# LTC6802.net
KiCad netlist of a schematic drawn in Altium Designer
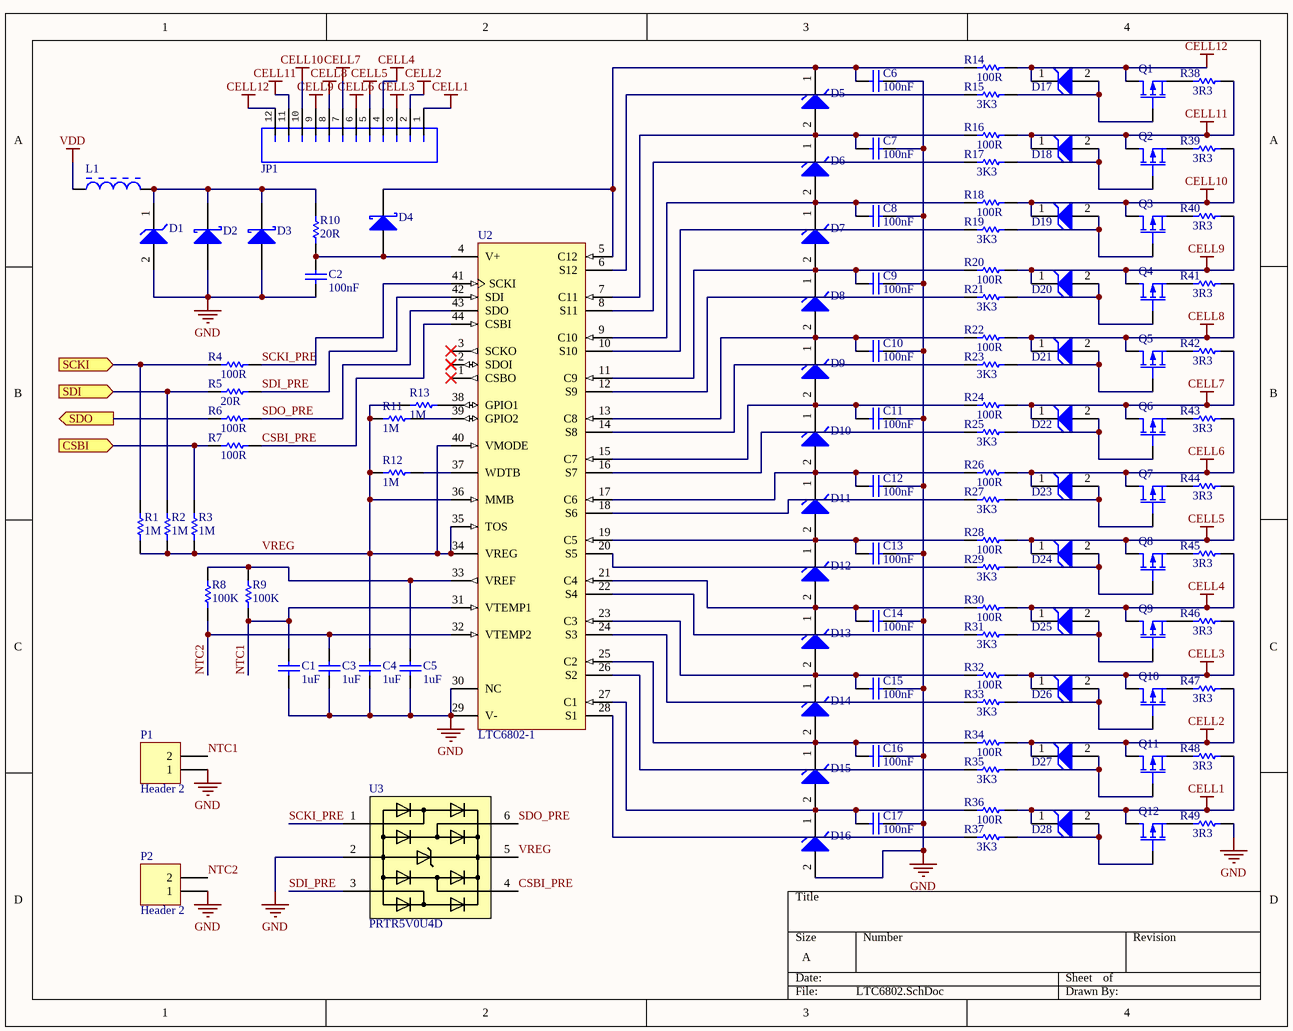
[diagram p0: LTC6802.SchDoc]

(export (version "E")
  (design (tool "Eeschema 10.0.6"))
  (components
    (comp (ref "C1")
      (value "1uF")
      (footprint "CAPC0603(1608)100_L")
      (description "CAP 1uF 6.3V Â±10% 0603 (1608 Metric) Thickness 1mm SMD")
      (fields (field (name "TOLERANCE") "Â±10%"))
      (libsource (lib "Altium Content Vault") (part "CAP"))
    )
    (comp (ref "C2")
      (value "100nF")
      (footprint "CAPC0603(1608)100_M")
      (description "CAP 100nF 100V Â±10% 0603 (1608 Metric) Thickness 1mm SMD")
      (fields (field (name "TOLERANCE") "Â±10%"))
      (libsource (lib "Altium Content Vault") (part "CAP"))
    )
    (comp (ref "C3")
      (value "1uF")
      (footprint "CAPC0603(1608)100_L")
      (description "CAP 1uF 6.3V Â±10% 0603 (1608 Metric) Thickness 1mm SMD")
      (fields (field (name "TOLERANCE") "Â±10%"))
      (libsource (lib "Altium Content Vault") (part "CAP"))
    )
    (comp (ref "C4")
      (value "1uF")
      (footprint "CAPC0603(1608)100_L")
      (description "CAP 1uF 6.3V Â±10% 0603 (1608 Metric) Thickness 1mm SMD")
      (fields (field (name "TOLERANCE") "Â±10%"))
      (libsource (lib "Altium Content Vault") (part "CAP"))
    )
    (comp (ref "C5")
      (value "1uF")
      (footprint "CAPC0603(1608)100_L")
      (description "CAP 1uF 6.3V Â±10% 0603 (1608 Metric) Thickness 1mm SMD")
      (fields (field (name "TOLERANCE") "Â±10%"))
      (libsource (lib "Altium Content Vault") (part "CAP"))
    )
    (comp (ref "C6")
      (value "100nF")
      (footprint "CAPC0603(1608)100_N")
      (description "CAP 100nF 6.3V Â±5% 0603 (1608 Metric) Thickness 1mm SMD")
      (fields (field (name "TOLERANCE") "Â±5%"))
      (libsource (lib "Altium Content Vault") (part "CAP"))
    )
    (comp (ref "C7")
      (value "100nF")
      (footprint "CAPC0603(1608)100_N")
      (description "CAP 100nF 6.3V Â±5% 0603 (1608 Metric) Thickness 1mm SMD")
      (fields (field (name "TOLERANCE") "Â±5%"))
      (libsource (lib "Altium Content Vault") (part "CAP"))
    )
    (comp (ref "C8")
      (value "100nF")
      (footprint "CAPC0603(1608)100_N")
      (description "CAP 100nF 6.3V Â±5% 0603 (1608 Metric) Thickness 1mm SMD")
      (fields (field (name "TOLERANCE") "Â±5%"))
      (libsource (lib "Altium Content Vault") (part "CAP"))
    )
    (comp (ref "C9")
      (value "100nF")
      (footprint "CAPC0603(1608)100_N")
      (description "CAP 100nF 6.3V Â±5% 0603 (1608 Metric) Thickness 1mm SMD")
      (fields (field (name "TOLERANCE") "Â±5%"))
      (libsource (lib "Altium Content Vault") (part "CAP"))
    )
    (comp (ref "C10")
      (value "100nF")
      (footprint "CAPC0603(1608)100_N")
      (description "CAP 100nF 6.3V Â±5% 0603 (1608 Metric) Thickness 1mm SMD")
      (fields (field (name "TOLERANCE") "Â±5%"))
      (libsource (lib "Altium Content Vault") (part "CAP"))
    )
    (comp (ref "C11")
      (value "100nF")
      (footprint "CAPC0603(1608)100_N")
      (description "CAP 100nF 6.3V Â±5% 0603 (1608 Metric) Thickness 1mm SMD")
      (fields (field (name "TOLERANCE") "Â±5%"))
      (libsource (lib "Altium Content Vault") (part "CAP"))
    )
    (comp (ref "C12")
      (value "100nF")
      (footprint "CAPC0603(1608)100_N")
      (description "CAP 100nF 6.3V Â±5% 0603 (1608 Metric) Thickness 1mm SMD")
      (fields (field (name "TOLERANCE") "Â±5%"))
      (libsource (lib "Altium Content Vault") (part "CAP"))
    )
    (comp (ref "C13")
      (value "100nF")
      (footprint "CAPC0603(1608)100_N")
      (description "CAP 100nF 6.3V Â±5% 0603 (1608 Metric) Thickness 1mm SMD")
      (fields (field (name "TOLERANCE") "Â±5%"))
      (libsource (lib "Altium Content Vault") (part "CAP"))
    )
    (comp (ref "C14")
      (value "100nF")
      (footprint "CAPC0603(1608)100_N")
      (description "CAP 100nF 6.3V Â±5% 0603 (1608 Metric) Thickness 1mm SMD")
      (fields (field (name "TOLERANCE") "Â±5%"))
      (libsource (lib "Altium Content Vault") (part "CAP"))
    )
    (comp (ref "C15")
      (value "100nF")
      (footprint "CAPC0603(1608)100_N")
      (description "CAP 100nF 6.3V Â±5% 0603 (1608 Metric) Thickness 1mm SMD")
      (fields (field (name "TOLERANCE") "Â±5%"))
      (libsource (lib "Altium Content Vault") (part "CAP"))
    )
    (comp (ref "C16")
      (value "100nF")
      (footprint "CAPC0603(1608)100_N")
      (description "CAP 100nF 6.3V Â±5% 0603 (1608 Metric) Thickness 1mm SMD")
      (fields (field (name "TOLERANCE") "Â±5%"))
      (libsource (lib "Altium Content Vault") (part "CAP"))
    )
    (comp (ref "C17")
      (value "100nF")
      (footprint "CAPC0603(1608)100_N")
      (description "CAP 100nF 6.3V Â±5% 0603 (1608 Metric) Thickness 1mm SMD")
      (fields (field (name "TOLERANCE") "Â±5%"))
      (libsource (lib "Altium Content Vault") (part "CAP"))
    )
    (comp (ref "D1") (value "~") (footprint "SOD-123") (libsource (lib "Components") (part "CMHZ5265B")))
    (comp (ref "D2")
      (value "~")
      (footprint "DIOD-SOD-123-2_V")
      (description "Surface Mount Schottky Barrier Diode, 100 V, -55 to 125 degC, 2-Pin SOD123, RoHS, Tape and Reel")
      (fields (field (name "PARTNUMBER") "BAT46W-7-F") (field (name "MANUFACTURER") "Diodes Inc"))
      (libsource (lib "Altium Content Vault") (part "DIOD-DSKY-A1K2-2"))
    )
    (comp (ref "D3")
      (value "~")
      (footprint "DIOD-SOD-123-2_V")
      (description "Surface Mount Schottky Barrier Diode, 100 V, -55 to 125 degC, 2-Pin SOD123, RoHS, Tape and Reel")
      (fields (field (name "PARTNUMBER") "BAT46W-7-F") (field (name "MANUFACTURER") "Diodes Inc"))
      (libsource (lib "Altium Content Vault") (part "DIOD-DSKY-A1K2-2"))
    )
    (comp (ref "D4")
      (value "~")
      (footprint "DIOD-SOD-123-2_V")
      (description "Surface Mount Schottky Barrier Diode, 100 V, -55 to 125 degC, 2-Pin SOD123, RoHS, Tape and Reel")
      (fields (field (name "PARTNUMBER") "BAT46W-7-F") (field (name "MANUFACTURER") "Diodes Inc"))
      (libsource (lib "Altium Content Vault") (part "DIOD-DSKY-A1K2-2"))
    )
    (comp (ref "D5")
      (value "~")
      (footprint "ONSC-SOD-323-2-477-02_V")
      (description "Zener Voltage Regulator, 300 mW, 2-Pin SOD-323, Tape and Reel")
      (fields (field (name "MANUFACTURER") "On Semiconductor") (field (name "PARTNUMBER") "MM3Z12VT1"))
      (libsource (lib "Altium Content Vault") (part "ONSC-K1A2-2"))
    )
    (comp (ref "D6")
      (value "~")
      (footprint "ONSC-SOD-323-2-477-02_V")
      (description "Zener Voltage Regulator, 300 mW, 2-Pin SOD-323, Tape and Reel")
      (fields (field (name "MANUFACTURER") "On Semiconductor") (field (name "PARTNUMBER") "MM3Z12VT1"))
      (libsource (lib "Altium Content Vault") (part "ONSC-K1A2-2"))
    )
    (comp (ref "D7")
      (value "~")
      (footprint "ONSC-SOD-323-2-477-02_V")
      (description "Zener Voltage Regulator, 300 mW, 2-Pin SOD-323, Tape and Reel")
      (fields (field (name "MANUFACTURER") "On Semiconductor") (field (name "PARTNUMBER") "MM3Z12VT1"))
      (libsource (lib "Altium Content Vault") (part "ONSC-K1A2-2"))
    )
    (comp (ref "D8")
      (value "~")
      (footprint "ONSC-SOD-323-2-477-02_V")
      (description "Zener Voltage Regulator, 300 mW, 2-Pin SOD-323, Tape and Reel")
      (fields (field (name "MANUFACTURER") "On Semiconductor") (field (name "PARTNUMBER") "MM3Z12VT1"))
      (libsource (lib "Altium Content Vault") (part "ONSC-K1A2-2"))
    )
    (comp (ref "D9")
      (value "~")
      (footprint "ONSC-SOD-323-2-477-02_V")
      (description "Zener Voltage Regulator, 300 mW, 2-Pin SOD-323, Tape and Reel")
      (fields (field (name "MANUFACTURER") "On Semiconductor") (field (name "PARTNUMBER") "MM3Z12VT1"))
      (libsource (lib "Altium Content Vault") (part "ONSC-K1A2-2"))
    )
    (comp (ref "D10")
      (value "~")
      (footprint "ONSC-SOD-323-2-477-02_V")
      (description "Zener Voltage Regulator, 300 mW, 2-Pin SOD-323, Tape and Reel")
      (fields (field (name "MANUFACTURER") "On Semiconductor") (field (name "PARTNUMBER") "MM3Z12VT1"))
      (libsource (lib "Altium Content Vault") (part "ONSC-K1A2-2"))
    )
    (comp (ref "D11")
      (value "~")
      (footprint "ONSC-SOD-323-2-477-02_V")
      (description "Zener Voltage Regulator, 300 mW, 2-Pin SOD-323, Tape and Reel")
      (fields (field (name "MANUFACTURER") "On Semiconductor") (field (name "PARTNUMBER") "MM3Z12VT1"))
      (libsource (lib "Altium Content Vault") (part "ONSC-K1A2-2"))
    )
    (comp (ref "D12")
      (value "~")
      (footprint "ONSC-SOD-323-2-477-02_V")
      (description "Zener Voltage Regulator, 300 mW, 2-Pin SOD-323, Tape and Reel")
      (fields (field (name "MANUFACTURER") "On Semiconductor") (field (name "PARTNUMBER") "MM3Z12VT1"))
      (libsource (lib "Altium Content Vault") (part "ONSC-K1A2-2"))
    )
    (comp (ref "D13")
      (value "~")
      (footprint "ONSC-SOD-323-2-477-02_V")
      (description "Zener Voltage Regulator, 300 mW, 2-Pin SOD-323, Tape and Reel")
      (fields (field (name "MANUFACTURER") "On Semiconductor") (field (name "PARTNUMBER") "MM3Z12VT1"))
      (libsource (lib "Altium Content Vault") (part "ONSC-K1A2-2"))
    )
    (comp (ref "D14")
      (value "~")
      (footprint "ONSC-SOD-323-2-477-02_V")
      (description "Zener Voltage Regulator, 300 mW, 2-Pin SOD-323, Tape and Reel")
      (fields (field (name "MANUFACTURER") "On Semiconductor") (field (name "PARTNUMBER") "MM3Z12VT1"))
      (libsource (lib "Altium Content Vault") (part "ONSC-K1A2-2"))
    )
    (comp (ref "D15")
      (value "~")
      (footprint "ONSC-SOD-323-2-477-02_V")
      (description "Zener Voltage Regulator, 300 mW, 2-Pin SOD-323, Tape and Reel")
      (fields (field (name "MANUFACTURER") "On Semiconductor") (field (name "PARTNUMBER") "MM3Z12VT1"))
      (libsource (lib "Altium Content Vault") (part "ONSC-K1A2-2"))
    )
    (comp (ref "D16")
      (value "~")
      (footprint "ONSC-SOD-323-2-477-02_V")
      (description "Zener Voltage Regulator, 300 mW, 2-Pin SOD-323, Tape and Reel")
      (fields (field (name "MANUFACTURER") "On Semiconductor") (field (name "PARTNUMBER") "MM3Z12VT1"))
      (libsource (lib "Altium Content Vault") (part "ONSC-K1A2-2"))
    )
    (comp (ref "D17")
      (value "~")
      (footprint "ONSC-SOD-323-2-477-02_V")
      (description "Zener Voltage Regulator, 300 mW, 2-Pin SOD-323, Tape and Reel")
      (fields (field (name "MANUFACTURER") "On Semiconductor") (field (name "PARTNUMBER") "MM3Z12VT1"))
      (libsource (lib "Altium Content Vault") (part "ONSC-K1A2-2"))
    )
    (comp (ref "D18")
      (value "~")
      (footprint "ONSC-SOD-323-2-477-02_V")
      (description "Zener Voltage Regulator, 300 mW, 2-Pin SOD-323, Tape and Reel")
      (fields (field (name "MANUFACTURER") "On Semiconductor") (field (name "PARTNUMBER") "MM3Z12VT1"))
      (libsource (lib "Altium Content Vault") (part "ONSC-K1A2-2"))
    )
    (comp (ref "D19")
      (value "~")
      (footprint "ONSC-SOD-323-2-477-02_V")
      (description "Zener Voltage Regulator, 300 mW, 2-Pin SOD-323, Tape and Reel")
      (fields (field (name "MANUFACTURER") "On Semiconductor") (field (name "PARTNUMBER") "MM3Z12VT1"))
      (libsource (lib "Altium Content Vault") (part "ONSC-K1A2-2"))
    )
    (comp (ref "D20")
      (value "~")
      (footprint "ONSC-SOD-323-2-477-02_V")
      (description "Zener Voltage Regulator, 300 mW, 2-Pin SOD-323, Tape and Reel")
      (fields (field (name "MANUFACTURER") "On Semiconductor") (field (name "PARTNUMBER") "MM3Z12VT1"))
      (libsource (lib "Altium Content Vault") (part "ONSC-K1A2-2"))
    )
    (comp (ref "D21")
      (value "~")
      (footprint "ONSC-SOD-323-2-477-02_V")
      (description "Zener Voltage Regulator, 300 mW, 2-Pin SOD-323, Tape and Reel")
      (fields (field (name "MANUFACTURER") "On Semiconductor") (field (name "PARTNUMBER") "MM3Z12VT1"))
      (libsource (lib "Altium Content Vault") (part "ONSC-K1A2-2"))
    )
    (comp (ref "D22")
      (value "~")
      (footprint "ONSC-SOD-323-2-477-02_V")
      (description "Zener Voltage Regulator, 300 mW, 2-Pin SOD-323, Tape and Reel")
      (fields (field (name "MANUFACTURER") "On Semiconductor") (field (name "PARTNUMBER") "MM3Z12VT1"))
      (libsource (lib "Altium Content Vault") (part "ONSC-K1A2-2"))
    )
    (comp (ref "D23")
      (value "~")
      (footprint "ONSC-SOD-323-2-477-02_V")
      (description "Zener Voltage Regulator, 300 mW, 2-Pin SOD-323, Tape and Reel")
      (fields (field (name "MANUFACTURER") "On Semiconductor") (field (name "PARTNUMBER") "MM3Z12VT1"))
      (libsource (lib "Altium Content Vault") (part "ONSC-K1A2-2"))
    )
    (comp (ref "D24")
      (value "~")
      (footprint "ONSC-SOD-323-2-477-02_V")
      (description "Zener Voltage Regulator, 300 mW, 2-Pin SOD-323, Tape and Reel")
      (fields (field (name "MANUFACTURER") "On Semiconductor") (field (name "PARTNUMBER") "MM3Z12VT1"))
      (libsource (lib "Altium Content Vault") (part "ONSC-K1A2-2"))
    )
    (comp (ref "D25")
      (value "~")
      (footprint "ONSC-SOD-323-2-477-02_V")
      (description "Zener Voltage Regulator, 300 mW, 2-Pin SOD-323, Tape and Reel")
      (fields (field (name "MANUFACTURER") "On Semiconductor") (field (name "PARTNUMBER") "MM3Z12VT1"))
      (libsource (lib "Altium Content Vault") (part "ONSC-K1A2-2"))
    )
    (comp (ref "D26")
      (value "~")
      (footprint "ONSC-SOD-323-2-477-02_V")
      (description "Zener Voltage Regulator, 300 mW, 2-Pin SOD-323, Tape and Reel")
      (fields (field (name "MANUFACTURER") "On Semiconductor") (field (name "PARTNUMBER") "MM3Z12VT1"))
      (libsource (lib "Altium Content Vault") (part "ONSC-K1A2-2"))
    )
    (comp (ref "D27")
      (value "~")
      (footprint "ONSC-SOD-323-2-477-02_V")
      (description "Zener Voltage Regulator, 300 mW, 2-Pin SOD-323, Tape and Reel")
      (fields (field (name "MANUFACTURER") "On Semiconductor") (field (name "PARTNUMBER") "MM3Z12VT1"))
      (libsource (lib "Altium Content Vault") (part "ONSC-K1A2-2"))
    )
    (comp (ref "D28")
      (value "~")
      (footprint "ONSC-SOD-323-2-477-02_V")
      (description "Zener Voltage Regulator, 300 mW, 2-Pin SOD-323, Tape and Reel")
      (fields (field (name "MANUFACTURER") "On Semiconductor") (field (name "PARTNUMBER") "MM3Z12VT1"))
      (libsource (lib "Altium Content Vault") (part "ONSC-K1A2-2"))
    )
    (comp (ref "JP1")
      (value "~")
      (footprint "JST-12-PTH")
      (libsource (lib "Components") (part "JST_12_RIGHT"))
    )
    (comp (ref "L1")
      (value "~")
      (footprint "MURA-BLM31-B60-CHIP-2_V1")
      (fields (field (name "MANUFACTURER") "Murata") (field (name "PARTNUMBER") "BLM31PG330SN1L"))
      (libsource (lib "Altium Content Vault") (part "MURA-FB-2"))
    )
    (comp (ref "P1")
      (value "Header 2")
      (footprint "HDR1X2")
      (description "Header, 2-Pin")
      (fields (field (name "PUBLISHER") "Altium Limited"))
      (libsource (lib "Miscellaneous Connectors") (part "Header 2"))
    )
    (comp (ref "P2")
      (value "Header 2")
      (footprint "HDR1X2")
      (description "Header, 2-Pin")
      (fields (field (name "PUBLISHER") "Altium Limited"))
      (libsource (lib "Miscellaneous Connectors") (part "Header 2"))
    )
    (comp (ref "Q1")
      (value "~")
      (footprint "SOT23-3")
      (description "P-Channel MOSFET")
      (fields (field (name "PUBLISHER") "Altium Limited"))
      (libsource (lib "Components") (part "MOSFET-P"))
    )
    (comp (ref "Q2")
      (value "~")
      (footprint "SOT23-3")
      (description "P-Channel MOSFET")
      (fields (field (name "PUBLISHER") "Altium Limited"))
      (libsource (lib "Components") (part "MOSFET-P"))
    )
    (comp (ref "Q3")
      (value "~")
      (footprint "SOT23-3")
      (description "P-Channel MOSFET")
      (fields (field (name "PUBLISHER") "Altium Limited"))
      (libsource (lib "Components") (part "MOSFET-P"))
    )
    (comp (ref "Q4")
      (value "~")
      (footprint "SOT23-3")
      (description "P-Channel MOSFET")
      (fields (field (name "PUBLISHER") "Altium Limited"))
      (libsource (lib "Components") (part "MOSFET-P"))
    )
    (comp (ref "Q5")
      (value "~")
      (footprint "SOT23-3")
      (description "P-Channel MOSFET")
      (fields (field (name "PUBLISHER") "Altium Limited"))
      (libsource (lib "Components") (part "MOSFET-P"))
    )
    (comp (ref "Q6")
      (value "~")
      (footprint "SOT23-3")
      (description "P-Channel MOSFET")
      (fields (field (name "PUBLISHER") "Altium Limited"))
      (libsource (lib "Components") (part "MOSFET-P"))
    )
    (comp (ref "Q7")
      (value "~")
      (footprint "SOT23-3")
      (description "P-Channel MOSFET")
      (fields (field (name "PUBLISHER") "Altium Limited"))
      (libsource (lib "Components") (part "MOSFET-P"))
    )
    (comp (ref "Q8")
      (value "~")
      (footprint "SOT23-3")
      (description "P-Channel MOSFET")
      (fields (field (name "PUBLISHER") "Altium Limited"))
      (libsource (lib "Components") (part "MOSFET-P"))
    )
    (comp (ref "Q9")
      (value "~")
      (footprint "SOT23-3")
      (description "P-Channel MOSFET")
      (fields (field (name "PUBLISHER") "Altium Limited"))
      (libsource (lib "Components") (part "MOSFET-P"))
    )
    (comp (ref "Q10")
      (value "~")
      (footprint "SOT23-3")
      (description "P-Channel MOSFET")
      (fields (field (name "PUBLISHER") "Altium Limited"))
      (libsource (lib "Components") (part "MOSFET-P"))
    )
    (comp (ref "Q11")
      (value "~")
      (footprint "SOT23-3")
      (description "P-Channel MOSFET")
      (fields (field (name "PUBLISHER") "Altium Limited"))
      (libsource (lib "Components") (part "MOSFET-P"))
    )
    (comp (ref "Q12")
      (value "~")
      (footprint "SOT23-3")
      (description "P-Channel MOSFET")
      (fields (field (name "PUBLISHER") "Altium Limited"))
      (libsource (lib "Components") (part "MOSFET-P"))
    )
    (comp (ref "R1")
      (value "1M")
      (footprint "RESC0603(1608)_N")
      (description "1M 0.1W 1% 0603 (1608 Metric)  SMD")
      (fields (field (name "POWER") "0.1 W") (field (name "TOLERANCE") "1 %"))
      (libsource (lib "Altium Content Vault") (part "RES"))
    )
    (comp (ref "R2")
      (value "1M")
      (footprint "RESC0603(1608)_N")
      (description "1M 0.1W 1% 0603 (1608 Metric)  SMD")
      (fields (field (name "POWER") "0.1 W") (field (name "TOLERANCE") "1 %"))
      (libsource (lib "Altium Content Vault") (part "RES"))
    )
    (comp (ref "R3")
      (value "1M")
      (footprint "RESC0603(1608)_N")
      (description "1M 0.1W 1% 0603 (1608 Metric)  SMD")
      (fields (field (name "POWER") "0.1 W") (field (name "TOLERANCE") "1 %"))
      (libsource (lib "Altium Content Vault") (part "RES"))
    )
    (comp (ref "R4")
      (value "100R")
      (footprint "RESC0603(1608)_M")
      (description "100R 0.1W 5% 0603 (1608 Metric)  SMD")
      (fields (field (name "TOLERANCE") "5 %") (field (name "POWER") "0.1 W"))
      (libsource (lib "Altium Content Vault") (part "RES"))
    )
    (comp (ref "R5")
      (value "20R")
      (footprint "RESC0603(1608)_M")
      (description "20R 0.1W 5% 0603 (1608 Metric)  SMD")
      (fields (field (name "TOLERANCE") "5 %") (field (name "POWER") "0.1 W"))
      (libsource (lib "Altium Content Vault") (part "RES"))
    )
    (comp (ref "R6")
      (value "100R")
      (footprint "RESC0603(1608)_M")
      (description "100R 0.1W 5% 0603 (1608 Metric)  SMD")
      (fields (field (name "TOLERANCE") "5 %") (field (name "POWER") "0.1 W"))
      (libsource (lib "Altium Content Vault") (part "RES"))
    )
    (comp (ref "R7")
      (value "100R")
      (footprint "RESC0603(1608)_M")
      (description "100R 0.1W 5% 0603 (1608 Metric)  SMD")
      (fields (field (name "TOLERANCE") "5 %") (field (name "POWER") "0.1 W"))
      (libsource (lib "Altium Content Vault") (part "RES"))
    )
    (comp (ref "R8")
      (value "100K")
      (footprint "RESC0603(1608)_M")
      (description "100K 0.1W 5% 0603 (1608 Metric)  SMD")
      (fields (field (name "TOLERANCE") "5 %") (field (name "POWER") "0.1 W"))
      (libsource (lib "Altium Content Vault") (part "RES"))
    )
    (comp (ref "R9")
      (value "100K")
      (footprint "RESC0603(1608)_M")
      (description "100K 0.1W 5% 0603 (1608 Metric)  SMD")
      (fields (field (name "TOLERANCE") "5 %") (field (name "POWER") "0.1 W"))
      (libsource (lib "Altium Content Vault") (part "RES"))
    )
    (comp (ref "R10")
      (value "20R")
      (footprint "RESC0603(1608)_M")
      (description "20R 0.1W 5% 0603 (1608 Metric)  SMD")
      (fields (field (name "TOLERANCE") "5 %") (field (name "POWER") "0.1 W"))
      (libsource (lib "Altium Content Vault") (part "RES"))
    )
    (comp (ref "R11")
      (value "1M")
      (footprint "RESC0603(1608)_N")
      (description "1M 0.1W 1% 0603 (1608 Metric)  SMD")
      (fields (field (name "POWER") "0.1 W") (field (name "TOLERANCE") "1 %"))
      (libsource (lib "Altium Content Vault") (part "RES"))
    )
    (comp (ref "R12")
      (value "1M")
      (footprint "RESC0603(1608)_N")
      (description "1M 0.1W 1% 0603 (1608 Metric)  SMD")
      (fields (field (name "POWER") "0.1 W") (field (name "TOLERANCE") "1 %"))
      (libsource (lib "Altium Content Vault") (part "RES"))
    )
    (comp (ref "R13")
      (value "1M")
      (footprint "RESC0603(1608)_N")
      (description "1M 0.1W 1% 0603 (1608 Metric)  SMD")
      (fields (field (name "POWER") "0.1 W") (field (name "TOLERANCE") "1 %"))
      (libsource (lib "Altium Content Vault") (part "RES"))
    )
    (comp (ref "R14")
      (value "100R")
      (footprint "RESC0603(1608)_M")
      (description "100R 0.1W 5% 0603 (1608 Metric)  SMD")
      (fields (field (name "TOLERANCE") "5 %") (field (name "POWER") "0.1 W"))
      (libsource (lib "Altium Content Vault") (part "RES"))
    )
    (comp (ref "R15")
      (value "3K3")
      (footprint "RESC0603(1608)_L")
      (description "3K3 0.1W 5% 0603 (1608 Metric)  SMD")
      (fields (field (name "TOLERANCE") "5 %") (field (name "POWER") "0.1 W"))
      (libsource (lib "Altium Content Vault") (part "RES"))
    )
    (comp (ref "R16")
      (value "100R")
      (footprint "RESC0603(1608)_M")
      (description "100R 0.1W 5% 0603 (1608 Metric)  SMD")
      (fields (field (name "TOLERANCE") "5 %") (field (name "POWER") "0.1 W"))
      (libsource (lib "Altium Content Vault") (part "RES"))
    )
    (comp (ref "R17")
      (value "3K3")
      (footprint "RESC0603(1608)_L")
      (description "3K3 0.1W 5% 0603 (1608 Metric)  SMD")
      (fields (field (name "TOLERANCE") "5 %") (field (name "POWER") "0.1 W"))
      (libsource (lib "Altium Content Vault") (part "RES"))
    )
    (comp (ref "R18")
      (value "100R")
      (footprint "RESC0603(1608)_M")
      (description "100R 0.1W 5% 0603 (1608 Metric)  SMD")
      (fields (field (name "TOLERANCE") "5 %") (field (name "POWER") "0.1 W"))
      (libsource (lib "Altium Content Vault") (part "RES"))
    )
    (comp (ref "R19")
      (value "3K3")
      (footprint "RESC0603(1608)_L")
      (description "3K3 0.1W 5% 0603 (1608 Metric)  SMD")
      (fields (field (name "TOLERANCE") "5 %") (field (name "POWER") "0.1 W"))
      (libsource (lib "Altium Content Vault") (part "RES"))
    )
    (comp (ref "R20")
      (value "100R")
      (footprint "RESC0603(1608)_M")
      (description "100R 0.1W 5% 0603 (1608 Metric)  SMD")
      (fields (field (name "TOLERANCE") "5 %") (field (name "POWER") "0.1 W"))
      (libsource (lib "Altium Content Vault") (part "RES"))
    )
    (comp (ref "R21")
      (value "3K3")
      (footprint "RESC0603(1608)_L")
      (description "3K3 0.1W 5% 0603 (1608 Metric)  SMD")
      (fields (field (name "TOLERANCE") "5 %") (field (name "POWER") "0.1 W"))
      (libsource (lib "Altium Content Vault") (part "RES"))
    )
    (comp (ref "R22")
      (value "100R")
      (footprint "RESC0603(1608)_M")
      (description "100R 0.1W 5% 0603 (1608 Metric)  SMD")
      (fields (field (name "TOLERANCE") "5 %") (field (name "POWER") "0.1 W"))
      (libsource (lib "Altium Content Vault") (part "RES"))
    )
    (comp (ref "R23")
      (value "3K3")
      (footprint "RESC0603(1608)_L")
      (description "3K3 0.1W 5% 0603 (1608 Metric)  SMD")
      (fields (field (name "TOLERANCE") "5 %") (field (name "POWER") "0.1 W"))
      (libsource (lib "Altium Content Vault") (part "RES"))
    )
    (comp (ref "R24")
      (value "100R")
      (footprint "RESC0603(1608)_M")
      (description "100R 0.1W 5% 0603 (1608 Metric)  SMD")
      (fields (field (name "TOLERANCE") "5 %") (field (name "POWER") "0.1 W"))
      (libsource (lib "Altium Content Vault") (part "RES"))
    )
    (comp (ref "R25")
      (value "3K3")
      (footprint "RESC0603(1608)_L")
      (description "3K3 0.1W 5% 0603 (1608 Metric)  SMD")
      (fields (field (name "TOLERANCE") "5 %") (field (name "POWER") "0.1 W"))
      (libsource (lib "Altium Content Vault") (part "RES"))
    )
    (comp (ref "R26")
      (value "100R")
      (footprint "RESC0603(1608)_M")
      (description "100R 0.1W 5% 0603 (1608 Metric)  SMD")
      (fields (field (name "TOLERANCE") "5 %") (field (name "POWER") "0.1 W"))
      (libsource (lib "Altium Content Vault") (part "RES"))
    )
    (comp (ref "R27")
      (value "3K3")
      (footprint "RESC0603(1608)_L")
      (description "3K3 0.1W 5% 0603 (1608 Metric)  SMD")
      (fields (field (name "TOLERANCE") "5 %") (field (name "POWER") "0.1 W"))
      (libsource (lib "Altium Content Vault") (part "RES"))
    )
    (comp (ref "R28")
      (value "100R")
      (footprint "RESC0603(1608)_M")
      (description "100R 0.1W 5% 0603 (1608 Metric)  SMD")
      (fields (field (name "TOLERANCE") "5 %") (field (name "POWER") "0.1 W"))
      (libsource (lib "Altium Content Vault") (part "RES"))
    )
    (comp (ref "R29")
      (value "3K3")
      (footprint "RESC0603(1608)_L")
      (description "3K3 0.1W 5% 0603 (1608 Metric)  SMD")
      (fields (field (name "TOLERANCE") "5 %") (field (name "POWER") "0.1 W"))
      (libsource (lib "Altium Content Vault") (part "RES"))
    )
    (comp (ref "R30")
      (value "100R")
      (footprint "RESC0603(1608)_M")
      (description "100R 0.1W 5% 0603 (1608 Metric)  SMD")
      (fields (field (name "TOLERANCE") "5 %") (field (name "POWER") "0.1 W"))
      (libsource (lib "Altium Content Vault") (part "RES"))
    )
    (comp (ref "R31")
      (value "3K3")
      (footprint "RESC0603(1608)_L")
      (description "3K3 0.1W 5% 0603 (1608 Metric)  SMD")
      (fields (field (name "TOLERANCE") "5 %") (field (name "POWER") "0.1 W"))
      (libsource (lib "Altium Content Vault") (part "RES"))
    )
    (comp (ref "R32")
      (value "100R")
      (footprint "RESC0603(1608)_M")
      (description "100R 0.1W 5% 0603 (1608 Metric)  SMD")
      (fields (field (name "TOLERANCE") "5 %") (field (name "POWER") "0.1 W"))
      (libsource (lib "Altium Content Vault") (part "RES"))
    )
    (comp (ref "R33")
      (value "3K3")
      (footprint "RESC0603(1608)_L")
      (description "3K3 0.1W 5% 0603 (1608 Metric)  SMD")
      (fields (field (name "TOLERANCE") "5 %") (field (name "POWER") "0.1 W"))
      (libsource (lib "Altium Content Vault") (part "RES"))
    )
    (comp (ref "R34")
      (value "100R")
      (footprint "RESC0603(1608)_M")
      (description "100R 0.1W 5% 0603 (1608 Metric)  SMD")
      (fields (field (name "TOLERANCE") "5 %") (field (name "POWER") "0.1 W"))
      (libsource (lib "Altium Content Vault") (part "RES"))
    )
    (comp (ref "R35")
      (value "3K3")
      (footprint "RESC0603(1608)_L")
      (description "3K3 0.1W 5% 0603 (1608 Metric)  SMD")
      (fields (field (name "TOLERANCE") "5 %") (field (name "POWER") "0.1 W"))
      (libsource (lib "Altium Content Vault") (part "RES"))
    )
    (comp (ref "R36")
      (value "100R")
      (footprint "RESC0603(1608)_M")
      (description "100R 0.1W 5% 0603 (1608 Metric)  SMD")
      (fields (field (name "TOLERANCE") "5 %") (field (name "POWER") "0.1 W"))
      (libsource (lib "Altium Content Vault") (part "RES"))
    )
    (comp (ref "R37")
      (value "3K3")
      (footprint "RESC0603(1608)_L")
      (description "3K3 0.1W 5% 0603 (1608 Metric)  SMD")
      (fields (field (name "TOLERANCE") "5 %") (field (name "POWER") "0.1 W"))
      (libsource (lib "Altium Content Vault") (part "RES"))
    )
    (comp (ref "R38")
      (value "3R3")
      (footprint "RESC2512(6432)_M")
      (description "3R3 1W 5% 2512 (6432 Metric)  SMD")
      (fields (field (name "TOLERANCE") "5 %") (field (name "POWER") "1 W"))
      (libsource (lib "Altium Content Vault") (part "RES"))
    )
    (comp (ref "R39")
      (value "3R3")
      (footprint "RESC2512(6432)_M")
      (description "3R3 1W 5% 2512 (6432 Metric)  SMD")
      (fields (field (name "TOLERANCE") "5 %") (field (name "POWER") "1 W"))
      (libsource (lib "Altium Content Vault") (part "RES"))
    )
    (comp (ref "R40")
      (value "3R3")
      (footprint "RESC2512(6432)_M")
      (description "3R3 1W 5% 2512 (6432 Metric)  SMD")
      (fields (field (name "TOLERANCE") "5 %") (field (name "POWER") "1 W"))
      (libsource (lib "Altium Content Vault") (part "RES"))
    )
    (comp (ref "R41")
      (value "3R3")
      (footprint "RESC2512(6432)_M")
      (description "3R3 1W 5% 2512 (6432 Metric)  SMD")
      (fields (field (name "TOLERANCE") "5 %") (field (name "POWER") "1 W"))
      (libsource (lib "Altium Content Vault") (part "RES"))
    )
    (comp (ref "R42")
      (value "3R3")
      (footprint "RESC2512(6432)_M")
      (description "3R3 1W 5% 2512 (6432 Metric)  SMD")
      (fields (field (name "TOLERANCE") "5 %") (field (name "POWER") "1 W"))
      (libsource (lib "Altium Content Vault") (part "RES"))
    )
    (comp (ref "R43")
      (value "3R3")
      (footprint "RESC2512(6432)_M")
      (description "3R3 1W 5% 2512 (6432 Metric)  SMD")
      (fields (field (name "TOLERANCE") "5 %") (field (name "POWER") "1 W"))
      (libsource (lib "Altium Content Vault") (part "RES"))
    )
    (comp (ref "R44")
      (value "3R3")
      (footprint "RESC2512(6432)_M")
      (description "3R3 1W 5% 2512 (6432 Metric)  SMD")
      (fields (field (name "TOLERANCE") "5 %") (field (name "POWER") "1 W"))
      (libsource (lib "Altium Content Vault") (part "RES"))
    )
    (comp (ref "R45")
      (value "3R3")
      (footprint "RESC2512(6432)_M")
      (description "3R3 1W 5% 2512 (6432 Metric)  SMD")
      (fields (field (name "TOLERANCE") "5 %") (field (name "POWER") "1 W"))
      (libsource (lib "Altium Content Vault") (part "RES"))
    )
    (comp (ref "R46")
      (value "3R3")
      (footprint "RESC2512(6432)_M")
      (description "3R3 1W 5% 2512 (6432 Metric)  SMD")
      (fields (field (name "TOLERANCE") "5 %") (field (name "POWER") "1 W"))
      (libsource (lib "Altium Content Vault") (part "RES"))
    )
    (comp (ref "R47")
      (value "3R3")
      (footprint "RESC2512(6432)_M")
      (description "3R3 1W 5% 2512 (6432 Metric)  SMD")
      (fields (field (name "TOLERANCE") "5 %") (field (name "POWER") "1 W"))
      (libsource (lib "Altium Content Vault") (part "RES"))
    )
    (comp (ref "R48")
      (value "3R3")
      (footprint "RESC2512(6432)_M")
      (description "3R3 1W 5% 2512 (6432 Metric)  SMD")
      (fields (field (name "TOLERANCE") "5 %") (field (name "POWER") "1 W"))
      (libsource (lib "Altium Content Vault") (part "RES"))
    )
    (comp (ref "R49")
      (value "3R3")
      (footprint "RESC2512(6432)_M")
      (description "3R3 1W 5% 2512 (6432 Metric)  SMD")
      (fields (field (name "TOLERANCE") "5 %") (field (name "POWER") "1 W"))
      (libsource (lib "Altium Content Vault") (part "RES"))
    )
    (comp (ref "U2")
      (value "LTC6802-1")
      (footprint "LT-G-44_M")
      (description "Multicell Battery Stack Monitor, 10 to 50 V Vin, 44-pin SOP (G-44), -40 to 85 degC, Pb-Free")
      (fields (field (name "PARTNUMBER") "LTC6802IG-1#PBF") (field (name "MANUFACTURER") "Linear Technology"))
      (libsource (lib "Altium Content Vault") (part "LT-LTC6802-1-G-44"))
    )
    (comp (ref "U3")
      (value "PRTR5V0U4D")
      (footprint "SOT457")
      (libsource (lib "Components") (part "PRTR5V0U4D"))
    )
  )
  (nets
    (net (code "1") (name "/CSBI") (class "Default")
      (node (ref "R3") (pin "2") (pinfunction "2_2") (pintype "passive"))
      (node (ref "R7") (pin "1") (pinfunction "1_1") (pintype "passive"))
    )
    (net (code "2") (name "/CSBI_PRE") (class "Default")
      (node (ref "R7") (pin "2") (pinfunction "2_2") (pintype "passive"))
      (node (ref "U2") (pin "44") (pinfunction "CSBI_44") (pintype "input"))
      (node (ref "U3") (pin "4") (pinfunction "4_4") (pintype "passive"))
    )
    (net (code "3") (name "/NTC1") (class "Default")
      (node (ref "C1") (pin "2") (pinfunction "2_2") (pintype "passive"))
      (node (ref "P1") (pin "2") (pinfunction "2_2") (pintype "passive"))
      (node (ref "R9") (pin "1") (pinfunction "1_1") (pintype "passive"))
      (node (ref "U2") (pin "31") (pinfunction "VTEMP1_31") (pintype "input"))
    )
    (net (code "4") (name "/NTC2") (class "Default")
      (node (ref "C3") (pin "2") (pinfunction "2_2") (pintype "passive"))
      (node (ref "P2") (pin "2") (pinfunction "2_2") (pintype "passive"))
      (node (ref "R8") (pin "1") (pinfunction "1_1") (pintype "passive"))
      (node (ref "U2") (pin "32") (pinfunction "VTEMP2_32") (pintype "input"))
    )
    (net (code "5") (name "/SCKI") (class "Default")
      (node (ref "R1") (pin "2") (pinfunction "2_2") (pintype "passive"))
      (node (ref "R4") (pin "1") (pinfunction "1_1") (pintype "passive"))
    )
    (net (code "6") (name "/SCKI_PRE") (class "Default")
      (node (ref "R4") (pin "2") (pinfunction "2_2") (pintype "passive"))
      (node (ref "U2") (pin "41") (pinfunction "SCKI_41") (pintype "input"))
      (node (ref "U3") (pin "1") (pinfunction "1_1") (pintype "passive"))
    )
    (net (code "7") (name "/SDI") (class "Default")
      (node (ref "R2") (pin "2") (pinfunction "2_2") (pintype "passive"))
      (node (ref "R5") (pin "1") (pinfunction "1_1") (pintype "passive"))
    )
    (net (code "8") (name "/SDI_PRE") (class "Default")
      (node (ref "R5") (pin "2") (pinfunction "2_2") (pintype "passive"))
      (node (ref "U2") (pin "42") (pinfunction "SDI_42") (pintype "input"))
      (node (ref "U3") (pin "3") (pinfunction "3_3") (pintype "passive"))
    )
    (net (code "9") (name "/SDO") (class "Default")
      (node (ref "R6") (pin "1") (pinfunction "1_1") (pintype "passive"))
    )
    (net (code "10") (name "/SDO_PRE") (class "Default")
      (node (ref "R6") (pin "2") (pinfunction "2_2") (pintype "passive"))
      (node (ref "U2") (pin "43") (pinfunction "SDO_43") (pintype "open_collector"))
      (node (ref "U3") (pin "6") (pinfunction "6_6") (pintype "passive"))
    )
    (net (code "11") (name "/VREG") (class "Default")
      (node (ref "C4") (pin "2") (pinfunction "2_2") (pintype "passive"))
      (node (ref "R1") (pin "1") (pinfunction "1_1") (pintype "passive"))
      (node (ref "R11") (pin "1") (pinfunction "1_1") (pintype "passive"))
      (node (ref "R12") (pin "1") (pinfunction "1_1") (pintype "passive"))
      (node (ref "R13") (pin "1") (pinfunction "1_1") (pintype "passive"))
      (node (ref "R2") (pin "1") (pinfunction "1_1") (pintype "passive"))
      (node (ref "R3") (pin "1") (pinfunction "1_1") (pintype "passive"))
      (node (ref "U2") (pin "34") (pinfunction "VREG_34") (pintype "power_in"))
      (node (ref "U2") (pin "35") (pinfunction "TOS_35") (pintype "input"))
      (node (ref "U2") (pin "36") (pinfunction "MMB_36") (pintype "input"))
      (node (ref "U2") (pin "40") (pinfunction "VMODE_40") (pintype "input"))
      (node (ref "U3") (pin "5") (pinfunction "5_5") (pintype "passive"))
    )
    (net (code "12") (name "CELL1") (class "Default")
      (node (ref "D28") (pin "1") (pinfunction "K_1") (pintype "passive"))
      (node (ref "JP1") (pin "1") (pinfunction "1_1") (pintype "passive"))
      (node (ref "Q12") (pin "1") (pinfunction "D_1") (pintype "passive"))
      (node (ref "R36") (pin "2") (pinfunction "2_2") (pintype "passive"))
      (node (ref "R48") (pin "1") (pinfunction "1_1") (pintype "passive"))
    )
    (net (code "13") (name "CELL2") (class "Default")
      (node (ref "D27") (pin "1") (pinfunction "K_1") (pintype "passive"))
      (node (ref "JP1") (pin "2") (pinfunction "2_2") (pintype "passive"))
      (node (ref "Q11") (pin "1") (pinfunction "D_1") (pintype "passive"))
      (node (ref "R34") (pin "2") (pinfunction "2_2") (pintype "passive"))
      (node (ref "R47") (pin "1") (pinfunction "1_1") (pintype "passive"))
    )
    (net (code "14") (name "CELL3") (class "Default")
      (node (ref "D26") (pin "1") (pinfunction "K_1") (pintype "passive"))
      (node (ref "JP1") (pin "3") (pinfunction "3_3") (pintype "passive"))
      (node (ref "Q10") (pin "1") (pinfunction "D_1") (pintype "passive"))
      (node (ref "R32") (pin "2") (pinfunction "2_2") (pintype "passive"))
      (node (ref "R46") (pin "1") (pinfunction "1_1") (pintype "passive"))
    )
    (net (code "15") (name "CELL4") (class "Default")
      (node (ref "D25") (pin "1") (pinfunction "K_1") (pintype "passive"))
      (node (ref "JP1") (pin "4") (pinfunction "4_4") (pintype "passive"))
      (node (ref "Q9") (pin "1") (pinfunction "D_1") (pintype "passive"))
      (node (ref "R30") (pin "2") (pinfunction "2_2") (pintype "passive"))
      (node (ref "R45") (pin "1") (pinfunction "1_1") (pintype "passive"))
    )
    (net (code "16") (name "CELL5") (class "Default")
      (node (ref "D24") (pin "1") (pinfunction "K_1") (pintype "passive"))
      (node (ref "JP1") (pin "5") (pinfunction "5_5") (pintype "passive"))
      (node (ref "Q8") (pin "1") (pinfunction "D_1") (pintype "passive"))
      (node (ref "R28") (pin "2") (pinfunction "2_2") (pintype "passive"))
      (node (ref "R44") (pin "1") (pinfunction "1_1") (pintype "passive"))
    )
    (net (code "17") (name "CELL6") (class "Default")
      (node (ref "D23") (pin "1") (pinfunction "K_1") (pintype "passive"))
      (node (ref "JP1") (pin "6") (pinfunction "6_6") (pintype "passive"))
      (node (ref "Q7") (pin "1") (pinfunction "D_1") (pintype "passive"))
      (node (ref "R26") (pin "2") (pinfunction "2_2") (pintype "passive"))
      (node (ref "R43") (pin "1") (pinfunction "1_1") (pintype "passive"))
    )
    (net (code "18") (name "CELL7") (class "Default")
      (node (ref "D22") (pin "1") (pinfunction "K_1") (pintype "passive"))
      (node (ref "JP1") (pin "7") (pinfunction "7_7") (pintype "passive"))
      (node (ref "Q6") (pin "1") (pinfunction "D_1") (pintype "passive"))
      (node (ref "R24") (pin "2") (pinfunction "2_2") (pintype "passive"))
      (node (ref "R42") (pin "1") (pinfunction "1_1") (pintype "passive"))
    )
    (net (code "19") (name "CELL8") (class "Default")
      (node (ref "D21") (pin "1") (pinfunction "K_1") (pintype "passive"))
      (node (ref "JP1") (pin "8") (pinfunction "8_8") (pintype "passive"))
      (node (ref "Q5") (pin "1") (pinfunction "D_1") (pintype "passive"))
      (node (ref "R22") (pin "2") (pinfunction "2_2") (pintype "passive"))
      (node (ref "R41") (pin "1") (pinfunction "1_1") (pintype "passive"))
    )
    (net (code "20") (name "CELL9") (class "Default")
      (node (ref "D20") (pin "1") (pinfunction "K_1") (pintype "passive"))
      (node (ref "JP1") (pin "9") (pinfunction "9_9") (pintype "passive"))
      (node (ref "Q4") (pin "1") (pinfunction "D_1") (pintype "passive"))
      (node (ref "R20") (pin "2") (pinfunction "2_2") (pintype "passive"))
      (node (ref "R40") (pin "1") (pinfunction "1_1") (pintype "passive"))
    )
    (net (code "21") (name "CELL10") (class "Default")
      (node (ref "D19") (pin "1") (pinfunction "K_1") (pintype "passive"))
      (node (ref "JP1") (pin "10") (pinfunction "10_10") (pintype "passive"))
      (node (ref "Q3") (pin "1") (pinfunction "D_1") (pintype "passive"))
      (node (ref "R18") (pin "2") (pinfunction "2_2") (pintype "passive"))
      (node (ref "R39") (pin "1") (pinfunction "1_1") (pintype "passive"))
    )
    (net (code "22") (name "CELL11") (class "Default")
      (node (ref "D18") (pin "1") (pinfunction "K_1") (pintype "passive"))
      (node (ref "JP1") (pin "11") (pinfunction "11_11") (pintype "passive"))
      (node (ref "Q2") (pin "1") (pinfunction "D_1") (pintype "passive"))
      (node (ref "R16") (pin "2") (pinfunction "2_2") (pintype "passive"))
      (node (ref "R38") (pin "1") (pinfunction "1_1") (pintype "passive"))
    )
    (net (code "23") (name "CELL12") (class "Default")
      (node (ref "D17") (pin "1") (pinfunction "K_1") (pintype "passive"))
      (node (ref "JP1") (pin "12") (pinfunction "12_12") (pintype "passive"))
      (node (ref "Q1") (pin "1") (pinfunction "D_1") (pintype "passive"))
      (node (ref "R14") (pin "2") (pinfunction "2_2") (pintype "passive"))
    )
    (net (code "24") (name "GND") (class "Default")
      (node (ref "C1") (pin "1") (pinfunction "1_1") (pintype "passive"))
      (node (ref "C10") (pin "1") (pinfunction "1_1") (pintype "passive"))
      (node (ref "C11") (pin "1") (pinfunction "1_1") (pintype "passive"))
      (node (ref "C12") (pin "1") (pinfunction "1_1") (pintype "passive"))
      (node (ref "C13") (pin "1") (pinfunction "1_1") (pintype "passive"))
      (node (ref "C14") (pin "1") (pinfunction "1_1") (pintype "passive"))
      (node (ref "C15") (pin "1") (pinfunction "1_1") (pintype "passive"))
      (node (ref "C16") (pin "1") (pinfunction "1_1") (pintype "passive"))
      (node (ref "C17") (pin "1") (pinfunction "1_1") (pintype "passive"))
      (node (ref "C2") (pin "1") (pinfunction "1_1") (pintype "passive"))
      (node (ref "C3") (pin "1") (pinfunction "1_1") (pintype "passive"))
      (node (ref "C4") (pin "1") (pinfunction "1_1") (pintype "passive"))
      (node (ref "C5") (pin "1") (pinfunction "1_1") (pintype "passive"))
      (node (ref "C6") (pin "1") (pinfunction "1_1") (pintype "passive"))
      (node (ref "C7") (pin "1") (pinfunction "1_1") (pintype "passive"))
      (node (ref "C8") (pin "1") (pinfunction "1_1") (pintype "passive"))
      (node (ref "C9") (pin "1") (pinfunction "1_1") (pintype "passive"))
      (node (ref "D1") (pin "2") (pinfunction "A_2") (pintype "passive"))
      (node (ref "D16") (pin "2") (pinfunction "A_2") (pintype "passive"))
      (node (ref "D2") (pin "1") (pinfunction "A_1") (pintype "passive"))
      (node (ref "D3") (pin "1") (pinfunction "A_1") (pintype "passive"))
      (node (ref "P1") (pin "1") (pinfunction "1_1") (pintype "passive"))
      (node (ref "P2") (pin "1") (pinfunction "1_1") (pintype "passive"))
      (node (ref "R49") (pin "1") (pinfunction "1_1") (pintype "passive"))
      (node (ref "U2") (pin "29") (pinfunction "V-_29") (pintype "power_in"))
      (node (ref "U2") (pin "30") (pinfunction "NC_30") (pintype "passive"))
      (node (ref "U3") (pin "2") (pinfunction "2_2") (pintype "passive"))
    )
    (net (code "25") (name "Net-(D1-K)") (class "Default")
      (node (ref "D1") (pin "1") (pinfunction "K_1") (pintype "passive"))
      (node (ref "D2") (pin "2") (pinfunction "K_2") (pintype "passive"))
      (node (ref "D3") (pin "2") (pinfunction "K_2") (pintype "passive"))
      (node (ref "L1") (pin "2") (pinfunction "2_2") (pintype "passive"))
      (node (ref "R10") (pin "2") (pinfunction "2_2") (pintype "passive"))
    )
    (net (code "26") (name "Net-(D4-A)") (class "Default")
      (node (ref "C2") (pin "2") (pinfunction "2_2") (pintype "passive"))
      (node (ref "D4") (pin "1") (pinfunction "A_1") (pintype "passive"))
      (node (ref "R10") (pin "1") (pinfunction "1_1") (pintype "passive"))
      (node (ref "U2") (pin "4") (pinfunction "V+_4") (pintype "power_in"))
    )
    (net (code "27") (name "Net-(D4-K)") (class "Default")
      (node (ref "C6") (pin "2") (pinfunction "2_2") (pintype "passive"))
      (node (ref "D4") (pin "2") (pinfunction "K_2") (pintype "passive"))
      (node (ref "D5") (pin "1") (pinfunction "K_1") (pintype "passive"))
      (node (ref "R14") (pin "1") (pinfunction "1_1") (pintype "passive"))
      (node (ref "U2") (pin "5") (pinfunction "C12_5") (pintype "input"))
    )
    (net (code "28") (name "Net-(D5-A)") (class "Default")
      (node (ref "C7") (pin "2") (pinfunction "2_2") (pintype "passive"))
      (node (ref "D5") (pin "2") (pinfunction "A_2") (pintype "passive"))
      (node (ref "D6") (pin "1") (pinfunction "K_1") (pintype "passive"))
      (node (ref "R16") (pin "1") (pinfunction "1_1") (pintype "passive"))
      (node (ref "U2") (pin "7") (pinfunction "C11_7") (pintype "input"))
    )
    (net (code "29") (name "Net-(D6-A)") (class "Default")
      (node (ref "C8") (pin "2") (pinfunction "2_2") (pintype "passive"))
      (node (ref "D6") (pin "2") (pinfunction "A_2") (pintype "passive"))
      (node (ref "D7") (pin "1") (pinfunction "K_1") (pintype "passive"))
      (node (ref "R18") (pin "1") (pinfunction "1_1") (pintype "passive"))
      (node (ref "U2") (pin "9") (pinfunction "C10_9") (pintype "input"))
    )
    (net (code "30") (name "Net-(D7-A)") (class "Default")
      (node (ref "C9") (pin "2") (pinfunction "2_2") (pintype "passive"))
      (node (ref "D7") (pin "2") (pinfunction "A_2") (pintype "passive"))
      (node (ref "D8") (pin "1") (pinfunction "K_1") (pintype "passive"))
      (node (ref "R20") (pin "1") (pinfunction "1_1") (pintype "passive"))
      (node (ref "U2") (pin "11") (pinfunction "C9_11") (pintype "input"))
    )
    (net (code "31") (name "Net-(D8-A)") (class "Default")
      (node (ref "C10") (pin "2") (pinfunction "2_2") (pintype "passive"))
      (node (ref "D8") (pin "2") (pinfunction "A_2") (pintype "passive"))
      (node (ref "D9") (pin "1") (pinfunction "K_1") (pintype "passive"))
      (node (ref "R22") (pin "1") (pinfunction "1_1") (pintype "passive"))
      (node (ref "U2") (pin "13") (pinfunction "C8_13") (pintype "input"))
    )
    (net (code "32") (name "Net-(D10-A)") (class "Default")
      (node (ref "C12") (pin "2") (pinfunction "2_2") (pintype "passive"))
      (node (ref "D10") (pin "2") (pinfunction "A_2") (pintype "passive"))
      (node (ref "D11") (pin "1") (pinfunction "K_1") (pintype "passive"))
      (node (ref "R26") (pin "1") (pinfunction "1_1") (pintype "passive"))
      (node (ref "U2") (pin "17") (pinfunction "C6_17") (pintype "input"))
    )
    (net (code "33") (name "Net-(D10-K)") (class "Default")
      (node (ref "C11") (pin "2") (pinfunction "2_2") (pintype "passive"))
      (node (ref "D10") (pin "1") (pinfunction "K_1") (pintype "passive"))
      (node (ref "D9") (pin "2") (pinfunction "A_2") (pintype "passive"))
      (node (ref "R24") (pin "1") (pinfunction "1_1") (pintype "passive"))
      (node (ref "U2") (pin "15") (pinfunction "C7_15") (pintype "input"))
    )
    (net (code "34") (name "Net-(D11-A)") (class "Default")
      (node (ref "C13") (pin "2") (pinfunction "2_2") (pintype "passive"))
      (node (ref "D11") (pin "2") (pinfunction "A_2") (pintype "passive"))
      (node (ref "D12") (pin "1") (pinfunction "K_1") (pintype "passive"))
      (node (ref "R28") (pin "1") (pinfunction "1_1") (pintype "passive"))
      (node (ref "U2") (pin "19") (pinfunction "C5_19") (pintype "input"))
    )
    (net (code "35") (name "Net-(D12-A)") (class "Default")
      (node (ref "C14") (pin "2") (pinfunction "2_2") (pintype "passive"))
      (node (ref "D12") (pin "2") (pinfunction "A_2") (pintype "passive"))
      (node (ref "D13") (pin "1") (pinfunction "K_1") (pintype "passive"))
      (node (ref "R30") (pin "1") (pinfunction "1_1") (pintype "passive"))
      (node (ref "U2") (pin "21") (pinfunction "C4_21") (pintype "input"))
    )
    (net (code "36") (name "Net-(D13-A)") (class "Default")
      (node (ref "C15") (pin "2") (pinfunction "2_2") (pintype "passive"))
      (node (ref "D13") (pin "2") (pinfunction "A_2") (pintype "passive"))
      (node (ref "D14") (pin "1") (pinfunction "K_1") (pintype "passive"))
      (node (ref "R32") (pin "1") (pinfunction "1_1") (pintype "passive"))
      (node (ref "U2") (pin "23") (pinfunction "C3_23") (pintype "input"))
    )
    (net (code "37") (name "Net-(D14-A)") (class "Default")
      (node (ref "C16") (pin "2") (pinfunction "2_2") (pintype "passive"))
      (node (ref "D14") (pin "2") (pinfunction "A_2") (pintype "passive"))
      (node (ref "D15") (pin "1") (pinfunction "K_1") (pintype "passive"))
      (node (ref "R34") (pin "1") (pinfunction "1_1") (pintype "passive"))
      (node (ref "U2") (pin "25") (pinfunction "C2_25") (pintype "input"))
    )
    (net (code "38") (name "Net-(D15-A)") (class "Default")
      (node (ref "C17") (pin "2") (pinfunction "2_2") (pintype "passive"))
      (node (ref "D15") (pin "2") (pinfunction "A_2") (pintype "passive"))
      (node (ref "D16") (pin "1") (pinfunction "K_1") (pintype "passive"))
      (node (ref "R36") (pin "1") (pinfunction "1_1") (pintype "passive"))
      (node (ref "U2") (pin "27") (pinfunction "C1_27") (pintype "input"))
    )
    (net (code "39") (name "Net-(D17-A)") (class "Default")
      (node (ref "D17") (pin "2") (pinfunction "A_2") (pintype "passive"))
      (node (ref "Q1") (pin "2") (pinfunction "G_2") (pintype "passive"))
      (node (ref "R15") (pin "2") (pinfunction "2_2") (pintype "passive"))
    )
    (net (code "40") (name "Net-(D18-A)") (class "Default")
      (node (ref "D18") (pin "2") (pinfunction "A_2") (pintype "passive"))
      (node (ref "Q2") (pin "2") (pinfunction "G_2") (pintype "passive"))
      (node (ref "R17") (pin "2") (pinfunction "2_2") (pintype "passive"))
    )
    (net (code "41") (name "Net-(D19-A)") (class "Default")
      (node (ref "D19") (pin "2") (pinfunction "A_2") (pintype "passive"))
      (node (ref "Q3") (pin "2") (pinfunction "G_2") (pintype "passive"))
      (node (ref "R19") (pin "2") (pinfunction "2_2") (pintype "passive"))
    )
    (net (code "42") (name "Net-(D20-A)") (class "Default")
      (node (ref "D20") (pin "2") (pinfunction "A_2") (pintype "passive"))
      (node (ref "Q4") (pin "2") (pinfunction "G_2") (pintype "passive"))
      (node (ref "R21") (pin "2") (pinfunction "2_2") (pintype "passive"))
    )
    (net (code "43") (name "Net-(D21-A)") (class "Default")
      (node (ref "D21") (pin "2") (pinfunction "A_2") (pintype "passive"))
      (node (ref "Q5") (pin "2") (pinfunction "G_2") (pintype "passive"))
      (node (ref "R23") (pin "2") (pinfunction "2_2") (pintype "passive"))
    )
    (net (code "44") (name "Net-(D22-A)") (class "Default")
      (node (ref "D22") (pin "2") (pinfunction "A_2") (pintype "passive"))
      (node (ref "Q6") (pin "2") (pinfunction "G_2") (pintype "passive"))
      (node (ref "R25") (pin "2") (pinfunction "2_2") (pintype "passive"))
    )
    (net (code "45") (name "Net-(D23-A)") (class "Default")
      (node (ref "D23") (pin "2") (pinfunction "A_2") (pintype "passive"))
      (node (ref "Q7") (pin "2") (pinfunction "G_2") (pintype "passive"))
      (node (ref "R27") (pin "2") (pinfunction "2_2") (pintype "passive"))
    )
    (net (code "46") (name "Net-(D24-A)") (class "Default")
      (node (ref "D24") (pin "2") (pinfunction "A_2") (pintype "passive"))
      (node (ref "Q8") (pin "2") (pinfunction "G_2") (pintype "passive"))
      (node (ref "R29") (pin "2") (pinfunction "2_2") (pintype "passive"))
    )
    (net (code "47") (name "Net-(D25-A)") (class "Default")
      (node (ref "D25") (pin "2") (pinfunction "A_2") (pintype "passive"))
      (node (ref "Q9") (pin "2") (pinfunction "G_2") (pintype "passive"))
      (node (ref "R31") (pin "2") (pinfunction "2_2") (pintype "passive"))
    )
    (net (code "48") (name "Net-(D26-A)") (class "Default")
      (node (ref "D26") (pin "2") (pinfunction "A_2") (pintype "passive"))
      (node (ref "Q10") (pin "2") (pinfunction "G_2") (pintype "passive"))
      (node (ref "R33") (pin "2") (pinfunction "2_2") (pintype "passive"))
    )
    (net (code "49") (name "Net-(D27-A)") (class "Default")
      (node (ref "D27") (pin "2") (pinfunction "A_2") (pintype "passive"))
      (node (ref "Q11") (pin "2") (pinfunction "G_2") (pintype "passive"))
      (node (ref "R35") (pin "2") (pinfunction "2_2") (pintype "passive"))
    )
    (net (code "50") (name "Net-(D28-A)") (class "Default")
      (node (ref "D28") (pin "2") (pinfunction "A_2") (pintype "passive"))
      (node (ref "Q12") (pin "2") (pinfunction "G_2") (pintype "passive"))
      (node (ref "R37") (pin "2") (pinfunction "2_2") (pintype "passive"))
    )
    (net (code "51") (name "Net-(Q1-S)") (class "Default")
      (node (ref "Q1") (pin "3") (pinfunction "S_3") (pintype "passive"))
      (node (ref "R38") (pin "2") (pinfunction "2_2") (pintype "passive"))
    )
    (net (code "52") (name "Net-(Q2-S)") (class "Default")
      (node (ref "Q2") (pin "3") (pinfunction "S_3") (pintype "passive"))
      (node (ref "R39") (pin "2") (pinfunction "2_2") (pintype "passive"))
    )
    (net (code "53") (name "Net-(Q3-S)") (class "Default")
      (node (ref "Q3") (pin "3") (pinfunction "S_3") (pintype "passive"))
      (node (ref "R40") (pin "2") (pinfunction "2_2") (pintype "passive"))
    )
    (net (code "54") (name "Net-(Q4-S)") (class "Default")
      (node (ref "Q4") (pin "3") (pinfunction "S_3") (pintype "passive"))
      (node (ref "R41") (pin "2") (pinfunction "2_2") (pintype "passive"))
    )
    (net (code "55") (name "Net-(Q5-S)") (class "Default")
      (node (ref "Q5") (pin "3") (pinfunction "S_3") (pintype "passive"))
      (node (ref "R42") (pin "2") (pinfunction "2_2") (pintype "passive"))
    )
    (net (code "56") (name "Net-(Q6-S)") (class "Default")
      (node (ref "Q6") (pin "3") (pinfunction "S_3") (pintype "passive"))
      (node (ref "R43") (pin "2") (pinfunction "2_2") (pintype "passive"))
    )
    (net (code "57") (name "Net-(Q7-S)") (class "Default")
      (node (ref "Q7") (pin "3") (pinfunction "S_3") (pintype "passive"))
      (node (ref "R44") (pin "2") (pinfunction "2_2") (pintype "passive"))
    )
    (net (code "58") (name "Net-(Q8-S)") (class "Default")
      (node (ref "Q8") (pin "3") (pinfunction "S_3") (pintype "passive"))
      (node (ref "R45") (pin "2") (pinfunction "2_2") (pintype "passive"))
    )
    (net (code "59") (name "Net-(Q9-S)") (class "Default")
      (node (ref "Q9") (pin "3") (pinfunction "S_3") (pintype "passive"))
      (node (ref "R46") (pin "2") (pinfunction "2_2") (pintype "passive"))
    )
    (net (code "60") (name "Net-(Q10-S)") (class "Default")
      (node (ref "Q10") (pin "3") (pinfunction "S_3") (pintype "passive"))
      (node (ref "R47") (pin "2") (pinfunction "2_2") (pintype "passive"))
    )
    (net (code "61") (name "Net-(Q11-S)") (class "Default")
      (node (ref "Q11") (pin "3") (pinfunction "S_3") (pintype "passive"))
      (node (ref "R48") (pin "2") (pinfunction "2_2") (pintype "passive"))
    )
    (net (code "62") (name "Net-(Q12-S)") (class "Default")
      (node (ref "Q12") (pin "3") (pinfunction "S_3") (pintype "passive"))
      (node (ref "R49") (pin "2") (pinfunction "2_2") (pintype "passive"))
    )
    (net (code "63") (name "Net-(U2-GPIO1)") (class "Default")
      (node (ref "R13") (pin "2") (pinfunction "2_2") (pintype "passive"))
      (node (ref "U2") (pin "38") (pinfunction "GPIO1_38") (pintype "bidirectional"))
    )
    (net (code "64") (name "Net-(U2-GPIO2)") (class "Default")
      (node (ref "R11") (pin "2") (pinfunction "2_2") (pintype "passive"))
      (node (ref "U2") (pin "39") (pinfunction "GPIO2_39") (pintype "bidirectional"))
    )
    (net (code "65") (name "Net-(U2-S1)") (class "Default")
      (node (ref "R37") (pin "1") (pinfunction "1_1") (pintype "passive"))
      (node (ref "U2") (pin "28") (pinfunction "S1_28") (pintype "tri_state"))
    )
    (net (code "66") (name "Net-(U2-S2)") (class "Default")
      (node (ref "R35") (pin "1") (pinfunction "1_1") (pintype "passive"))
      (node (ref "U2") (pin "26") (pinfunction "S2_26") (pintype "tri_state"))
    )
    (net (code "67") (name "Net-(U2-S3)") (class "Default")
      (node (ref "R33") (pin "1") (pinfunction "1_1") (pintype "passive"))
      (node (ref "U2") (pin "24") (pinfunction "S3_24") (pintype "tri_state"))
    )
    (net (code "68") (name "Net-(U2-S4)") (class "Default")
      (node (ref "R31") (pin "1") (pinfunction "1_1") (pintype "passive"))
      (node (ref "U2") (pin "22") (pinfunction "S4_22") (pintype "tri_state"))
    )
    (net (code "69") (name "Net-(U2-S5)") (class "Default")
      (node (ref "R29") (pin "1") (pinfunction "1_1") (pintype "passive"))
      (node (ref "U2") (pin "20") (pinfunction "S5_20") (pintype "tri_state"))
    )
    (net (code "70") (name "Net-(U2-S6)") (class "Default")
      (node (ref "R27") (pin "1") (pinfunction "1_1") (pintype "passive"))
      (node (ref "U2") (pin "18") (pinfunction "S6_18") (pintype "tri_state"))
    )
    (net (code "71") (name "Net-(U2-S7)") (class "Default")
      (node (ref "R25") (pin "1") (pinfunction "1_1") (pintype "passive"))
      (node (ref "U2") (pin "16") (pinfunction "S7_16") (pintype "tri_state"))
    )
    (net (code "72") (name "Net-(U2-S8)") (class "Default")
      (node (ref "R23") (pin "1") (pinfunction "1_1") (pintype "passive"))
      (node (ref "U2") (pin "14") (pinfunction "S8_14") (pintype "tri_state"))
    )
    (net (code "73") (name "Net-(U2-S9)") (class "Default")
      (node (ref "R21") (pin "1") (pinfunction "1_1") (pintype "passive"))
      (node (ref "U2") (pin "12") (pinfunction "S9_12") (pintype "tri_state"))
    )
    (net (code "74") (name "Net-(U2-S10)") (class "Default")
      (node (ref "R19") (pin "1") (pinfunction "1_1") (pintype "passive"))
      (node (ref "U2") (pin "10") (pinfunction "S10_10") (pintype "tri_state"))
    )
    (net (code "75") (name "Net-(U2-S11)") (class "Default")
      (node (ref "R17") (pin "1") (pinfunction "1_1") (pintype "passive"))
      (node (ref "U2") (pin "8") (pinfunction "S11_8") (pintype "tri_state"))
    )
    (net (code "76") (name "Net-(U2-S12)") (class "Default")
      (node (ref "R15") (pin "1") (pinfunction "1_1") (pintype "passive"))
      (node (ref "U2") (pin "6") (pinfunction "S12_6") (pintype "tri_state"))
    )
    (net (code "77") (name "Net-(U2-VREF)") (class "Default")
      (node (ref "C5") (pin "2") (pinfunction "2_2") (pintype "passive"))
      (node (ref "R8") (pin "2") (pinfunction "2_2") (pintype "passive"))
      (node (ref "R9") (pin "2") (pinfunction "2_2") (pintype "passive"))
      (node (ref "U2") (pin "33") (pinfunction "VREF_33") (pintype "output"))
    )
    (net (code "78") (name "Net-(U2-WDTB)") (class "Default")
      (node (ref "R12") (pin "2") (pinfunction "2_2") (pintype "passive"))
      (node (ref "U2") (pin "37") (pinfunction "WDTB_37") (pintype "open_collector"))
    )
    (net (code "79") (name "VDD") (class "Default")
      (node (ref "L1") (pin "1") (pinfunction "1_1") (pintype "passive"))
    )
    (net (code "80") (name "unconnected-(U2-CSBO-Pad1)") (class "Default")
      (node (ref "U2") (pin "1") (pinfunction "CSBO_1") (pintype "output+no_connect"))
    )
    (net (code "81") (name "unconnected-(U2-SCKO-Pad3)") (class "Default")
      (node (ref "U2") (pin "3") (pinfunction "SCKO_3") (pintype "output+no_connect"))
    )
    (net (code "82") (name "unconnected-(U2-SDOI-Pad2)") (class "Default")
      (node (ref "U2") (pin "2") (pinfunction "SDOI_2") (pintype "bidirectional+no_connect"))
    )
  )
)
